# scoreboard.net
KiCad netlist of a schematic drawn in EAGLE
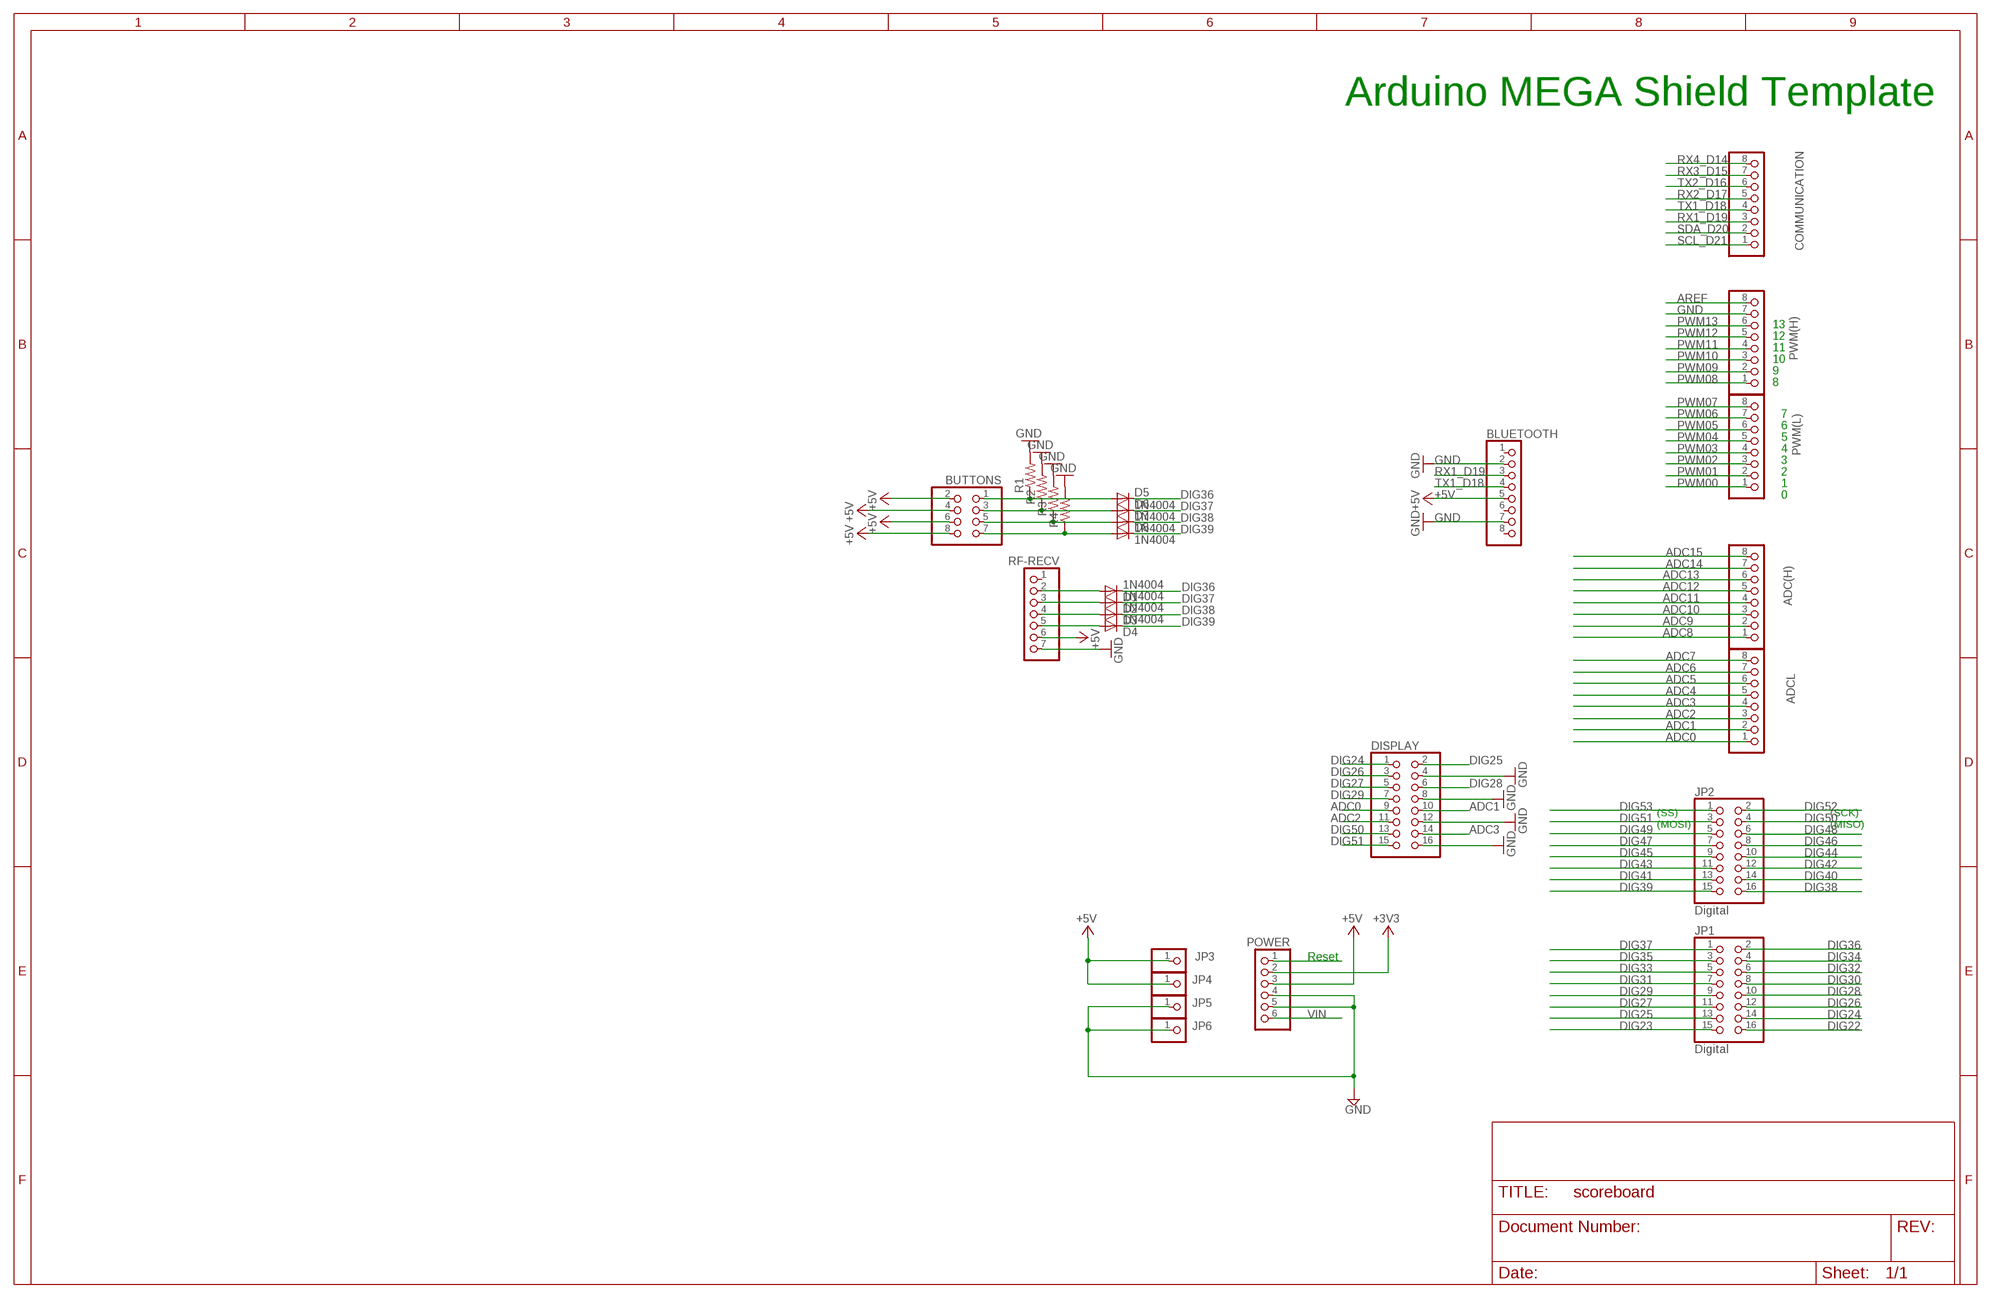
[diagram p0: schematic, sheet 1]

(export (version "E")
  (design (tool "Eeschema 10.0.6"))
  (components
    (comp (ref "ADC(H)")
      (value "PINHD-1X8")
      (footprint "eagle-import:1X08")
      (libsource (lib "eagle-import") (part "PINHD-1X8"))
    )
    (comp (ref "ADCL")
      (value "PINHD-1X8")
      (footprint "eagle-import:1X08")
      (libsource (lib "eagle-import") (part "PINHD-1X8"))
    )
    (comp (ref "BLUETOOTH")
      (value "PINHD-1X8")
      (footprint "eagle-import:1X08")
      (libsource (lib "eagle-import") (part "PINHD-1X8"))
    )
    (comp (ref "BUTTONS")
      (value "PINHD-2X4")
      (footprint "eagle-import:2X04")
      (libsource (lib "eagle-import") (part "PINHD-2X4"))
    )
    (comp (ref "COMMUNICATION")
      (value "PINHD-1X8")
      (footprint "eagle-import:1X08")
      (libsource (lib "eagle-import") (part "PINHD-1X8"))
    )
    (comp (ref "D1")
      (value "1N4004")
      (footprint "eagle-import:DO41-10")
      (libsource (lib "eagle-import") (part "1N4004"))
    )
    (comp (ref "D2")
      (value "1N4004")
      (footprint "eagle-import:DO41-10")
      (libsource (lib "eagle-import") (part "1N4004"))
    )
    (comp (ref "D3")
      (value "1N4004")
      (footprint "eagle-import:DO41-10")
      (libsource (lib "eagle-import") (part "1N4004"))
    )
    (comp (ref "D4")
      (value "1N4004")
      (footprint "eagle-import:DO41-10")
      (libsource (lib "eagle-import") (part "1N4004"))
    )
    (comp (ref "D5")
      (value "1N4004")
      (footprint "eagle-import:DO41-10")
      (libsource (lib "eagle-import") (part "1N4004"))
    )
    (comp (ref "D6")
      (value "1N4004")
      (footprint "eagle-import:DO41-10")
      (libsource (lib "eagle-import") (part "1N4004"))
    )
    (comp (ref "D7")
      (value "1N4004")
      (footprint "eagle-import:DO41-10")
      (libsource (lib "eagle-import") (part "1N4004"))
    )
    (comp (ref "D8")
      (value "1N4004")
      (footprint "eagle-import:DO41-10")
      (libsource (lib "eagle-import") (part "1N4004"))
    )
    (comp (ref "DISPLAY")
      (value "PINHD-2X8")
      (footprint "eagle-import:2X08")
      (libsource (lib "eagle-import") (part "PINHD-2X8"))
    )
    (comp (ref "JP1")
      (value "Digital")
      (footprint "eagle-import:2X08")
      (libsource (lib "eagle-import") (part "PINHD-2X8"))
    )
    (comp (ref "JP2")
      (value "Digital")
      (footprint "eagle-import:2X08")
      (libsource (lib "eagle-import") (part "PINHD-2X8"))
    )
    (comp (ref "JP3")
      (value "PINHD-1X1")
      (footprint "eagle-import:1X01")
      (libsource (lib "eagle-import") (part "PINHD-1X1"))
    )
    (comp (ref "JP4")
      (value "PINHD-1X1")
      (footprint "eagle-import:1X01")
      (libsource (lib "eagle-import") (part "PINHD-1X1"))
    )
    (comp (ref "JP5")
      (value "PINHD-1X1")
      (footprint "eagle-import:1X01")
      (libsource (lib "eagle-import") (part "PINHD-1X1"))
    )
    (comp (ref "JP6")
      (value "PINHD-1X1")
      (footprint "eagle-import:1X01")
      (libsource (lib "eagle-import") (part "PINHD-1X1"))
    )
    (comp (ref "POWER")
      (value "PINHD-1X6")
      (footprint "eagle-import:1X06")
      (libsource (lib "eagle-import") (part "PINHD-1X6"))
    )
    (comp (ref "PWM(H)")
      (value "PINHD-1X8")
      (footprint "eagle-import:1X08")
      (libsource (lib "eagle-import") (part "PINHD-1X8"))
    )
    (comp (ref "PWM(L)")
      (value "PINHD-1X8")
      (footprint "eagle-import:1X08")
      (libsource (lib "eagle-import") (part "PINHD-1X8"))
    )
    (comp (ref "R1")
      (value "FLIPFLOP-RES")
      (footprint "eagle-import:0805-THM")
      (libsource (lib "eagle-import") (part "FLIPFLOP-RES"))
    )
    (comp (ref "R2")
      (value "FLIPFLOP-RES")
      (footprint "eagle-import:0805-THM")
      (libsource (lib "eagle-import") (part "FLIPFLOP-RES"))
    )
    (comp (ref "R3")
      (value "FLIPFLOP-RES")
      (footprint "eagle-import:0805-THM")
      (libsource (lib "eagle-import") (part "FLIPFLOP-RES"))
    )
    (comp (ref "R4")
      (value "FLIPFLOP-RES")
      (footprint "eagle-import:0805-THM")
      (libsource (lib "eagle-import") (part "FLIPFLOP-RES"))
    )
    (comp (ref "RF-RECV")
      (value "PINHD-1X7")
      (footprint "eagle-import:1X07")
      (libsource (lib "eagle-import") (part "PINHD-1X7"))
    )
  )
  (nets
    (net (code "1") (name "+3V3") (class "Default")
      (node (ref "POWER") (pin "2") (pinfunction "2_2") (pintype "passive"))
    )
    (net (code "2") (name "+5V") (class "Default")
      (node (ref "BLUETOOTH") (pin "5") (pinfunction "5_5") (pintype "passive"))
      (node (ref "BUTTONS") (pin "2") (pinfunction "2_2") (pintype "passive"))
      (node (ref "BUTTONS") (pin "4") (pinfunction "4_4") (pintype "passive"))
      (node (ref "BUTTONS") (pin "6") (pinfunction "6_6") (pintype "passive"))
      (node (ref "BUTTONS") (pin "8") (pinfunction "8_8") (pintype "passive"))
      (node (ref "JP3") (pin "1") (pinfunction "1_1") (pintype "passive"))
      (node (ref "JP4") (pin "1") (pinfunction "1_1") (pintype "passive"))
      (node (ref "POWER") (pin "3") (pinfunction "3_3") (pintype "passive"))
      (node (ref "RF-RECV") (pin "6") (pinfunction "6_6") (pintype "passive"))
    )
    (net (code "3") (name "/ADC0") (class "Default")
      (node (ref "ADCL") (pin "1") (pinfunction "1_1") (pintype "passive"))
      (node (ref "DISPLAY") (pin "9") (pinfunction "9_9") (pintype "passive"))
    )
    (net (code "4") (name "/ADC1") (class "Default")
      (node (ref "ADCL") (pin "2") (pinfunction "2_2") (pintype "passive"))
      (node (ref "DISPLAY") (pin "10") (pinfunction "10_10") (pintype "passive"))
    )
    (net (code "5") (name "/ADC2") (class "Default")
      (node (ref "ADCL") (pin "3") (pinfunction "3_3") (pintype "passive"))
      (node (ref "DISPLAY") (pin "11") (pinfunction "11_11") (pintype "passive"))
    )
    (net (code "6") (name "/ADC3") (class "Default")
      (node (ref "ADCL") (pin "4") (pinfunction "4_4") (pintype "passive"))
      (node (ref "DISPLAY") (pin "14") (pinfunction "14_14") (pintype "passive"))
    )
    (net (code "7") (name "/ADC4") (class "Default")
      (node (ref "ADCL") (pin "5") (pinfunction "5_5") (pintype "passive"))
    )
    (net (code "8") (name "/ADC5") (class "Default")
      (node (ref "ADCL") (pin "6") (pinfunction "6_6") (pintype "passive"))
    )
    (net (code "9") (name "/ADC6") (class "Default")
      (node (ref "ADCL") (pin "7") (pinfunction "7_7") (pintype "passive"))
    )
    (net (code "10") (name "/ADC7") (class "Default")
      (node (ref "ADCL") (pin "8") (pinfunction "8_8") (pintype "passive"))
    )
    (net (code "11") (name "/ADC8") (class "Default")
      (node (ref "ADC(H)") (pin "1") (pinfunction "1_1") (pintype "passive"))
    )
    (net (code "12") (name "/ADC9") (class "Default")
      (node (ref "ADC(H)") (pin "2") (pinfunction "2_2") (pintype "passive"))
    )
    (net (code "13") (name "/ADC10") (class "Default")
      (node (ref "ADC(H)") (pin "3") (pinfunction "3_3") (pintype "passive"))
    )
    (net (code "14") (name "/ADC11") (class "Default")
      (node (ref "ADC(H)") (pin "4") (pinfunction "4_4") (pintype "passive"))
    )
    (net (code "15") (name "/ADC12") (class "Default")
      (node (ref "ADC(H)") (pin "5") (pinfunction "5_5") (pintype "passive"))
    )
    (net (code "16") (name "/ADC13") (class "Default")
      (node (ref "ADC(H)") (pin "6") (pinfunction "6_6") (pintype "passive"))
    )
    (net (code "17") (name "/ADC14") (class "Default")
      (node (ref "ADC(H)") (pin "7") (pinfunction "7_7") (pintype "passive"))
    )
    (net (code "18") (name "/ADC15") (class "Default")
      (node (ref "ADC(H)") (pin "8") (pinfunction "8_8") (pintype "passive"))
    )
    (net (code "19") (name "/AREF") (class "Default")
      (node (ref "PWM(H)") (pin "8") (pinfunction "8_8") (pintype "passive"))
    )
    (net (code "20") (name "/DIG22") (class "Default")
      (node (ref "JP1") (pin "16") (pinfunction "16_16") (pintype "passive"))
    )
    (net (code "21") (name "/DIG23") (class "Default")
      (node (ref "JP1") (pin "15") (pinfunction "15_15") (pintype "passive"))
    )
    (net (code "22") (name "/DIG24") (class "Default")
      (node (ref "DISPLAY") (pin "1") (pinfunction "1_1") (pintype "passive"))
      (node (ref "JP1") (pin "14") (pinfunction "14_14") (pintype "passive"))
    )
    (net (code "23") (name "/DIG25") (class "Default")
      (node (ref "DISPLAY") (pin "2") (pinfunction "2_2") (pintype "passive"))
      (node (ref "JP1") (pin "13") (pinfunction "13_13") (pintype "passive"))
    )
    (net (code "24") (name "/DIG26") (class "Default")
      (node (ref "DISPLAY") (pin "3") (pinfunction "3_3") (pintype "passive"))
      (node (ref "JP1") (pin "12") (pinfunction "12_12") (pintype "passive"))
    )
    (net (code "25") (name "/DIG27") (class "Default")
      (node (ref "DISPLAY") (pin "5") (pinfunction "5_5") (pintype "passive"))
      (node (ref "JP1") (pin "11") (pinfunction "11_11") (pintype "passive"))
    )
    (net (code "26") (name "/DIG28") (class "Default")
      (node (ref "DISPLAY") (pin "6") (pinfunction "6_6") (pintype "passive"))
      (node (ref "JP1") (pin "10") (pinfunction "10_10") (pintype "passive"))
    )
    (net (code "27") (name "/DIG29") (class "Default")
      (node (ref "DISPLAY") (pin "7") (pinfunction "7_7") (pintype "passive"))
      (node (ref "JP1") (pin "9") (pinfunction "9_9") (pintype "passive"))
    )
    (net (code "28") (name "/DIG30") (class "Default")
      (node (ref "JP1") (pin "8") (pinfunction "8_8") (pintype "passive"))
    )
    (net (code "29") (name "/DIG31") (class "Default")
      (node (ref "JP1") (pin "7") (pinfunction "7_7") (pintype "passive"))
    )
    (net (code "30") (name "/DIG32") (class "Default")
      (node (ref "JP1") (pin "6") (pinfunction "6_6") (pintype "passive"))
    )
    (net (code "31") (name "/DIG33") (class "Default")
      (node (ref "JP1") (pin "5") (pinfunction "5_5") (pintype "passive"))
    )
    (net (code "32") (name "/DIG34") (class "Default")
      (node (ref "JP1") (pin "4") (pinfunction "4_4") (pintype "passive"))
    )
    (net (code "33") (name "/DIG35") (class "Default")
      (node (ref "JP1") (pin "3") (pinfunction "3_3") (pintype "passive"))
    )
    (net (code "34") (name "/DIG36") (class "Default")
      (node (ref "D1") (pin "C") (pinfunction "C_C") (pintype "passive"))
      (node (ref "D5") (pin "C") (pinfunction "C_C") (pintype "passive"))
      (node (ref "JP1") (pin "2") (pinfunction "2_2") (pintype "passive"))
    )
    (net (code "35") (name "/DIG37") (class "Default")
      (node (ref "D2") (pin "C") (pinfunction "C_C") (pintype "passive"))
      (node (ref "D6") (pin "C") (pinfunction "C_C") (pintype "passive"))
      (node (ref "JP1") (pin "1") (pinfunction "1_1") (pintype "passive"))
    )
    (net (code "36") (name "/DIG38") (class "Default")
      (node (ref "D3") (pin "C") (pinfunction "C_C") (pintype "passive"))
      (node (ref "D7") (pin "C") (pinfunction "C_C") (pintype "passive"))
      (node (ref "JP2") (pin "16") (pinfunction "16_16") (pintype "passive"))
    )
    (net (code "37") (name "/DIG39") (class "Default")
      (node (ref "D4") (pin "C") (pinfunction "C_C") (pintype "passive"))
      (node (ref "D8") (pin "C") (pinfunction "C_C") (pintype "passive"))
      (node (ref "JP2") (pin "15") (pinfunction "15_15") (pintype "passive"))
    )
    (net (code "38") (name "/DIG40") (class "Default")
      (node (ref "JP2") (pin "14") (pinfunction "14_14") (pintype "passive"))
    )
    (net (code "39") (name "/DIG41") (class "Default")
      (node (ref "JP2") (pin "13") (pinfunction "13_13") (pintype "passive"))
    )
    (net (code "40") (name "/DIG42") (class "Default")
      (node (ref "JP2") (pin "12") (pinfunction "12_12") (pintype "passive"))
    )
    (net (code "41") (name "/DIG43") (class "Default")
      (node (ref "JP2") (pin "11") (pinfunction "11_11") (pintype "passive"))
    )
    (net (code "42") (name "/DIG44") (class "Default")
      (node (ref "JP2") (pin "10") (pinfunction "10_10") (pintype "passive"))
    )
    (net (code "43") (name "/DIG45") (class "Default")
      (node (ref "JP2") (pin "9") (pinfunction "9_9") (pintype "passive"))
    )
    (net (code "44") (name "/DIG46") (class "Default")
      (node (ref "JP2") (pin "8") (pinfunction "8_8") (pintype "passive"))
    )
    (net (code "45") (name "/DIG47") (class "Default")
      (node (ref "JP2") (pin "7") (pinfunction "7_7") (pintype "passive"))
    )
    (net (code "46") (name "/DIG48") (class "Default")
      (node (ref "JP2") (pin "6") (pinfunction "6_6") (pintype "passive"))
    )
    (net (code "47") (name "/DIG49") (class "Default")
      (node (ref "JP2") (pin "5") (pinfunction "5_5") (pintype "passive"))
    )
    (net (code "48") (name "/DIG50") (class "Default")
      (node (ref "DISPLAY") (pin "13") (pinfunction "13_13") (pintype "passive"))
      (node (ref "JP2") (pin "4") (pinfunction "4_4") (pintype "passive"))
    )
    (net (code "49") (name "/DIG51") (class "Default")
      (node (ref "DISPLAY") (pin "15") (pinfunction "15_15") (pintype "passive"))
      (node (ref "JP2") (pin "3") (pinfunction "3_3") (pintype "passive"))
    )
    (net (code "50") (name "/DIG52") (class "Default")
      (node (ref "JP2") (pin "2") (pinfunction "2_2") (pintype "passive"))
    )
    (net (code "51") (name "/DIG53") (class "Default")
      (node (ref "JP2") (pin "1") (pinfunction "1_1") (pintype "passive"))
    )
    (net (code "52") (name "/PWM00") (class "Default")
      (node (ref "PWM(L)") (pin "1") (pinfunction "1_1") (pintype "passive"))
    )
    (net (code "53") (name "/PWM01") (class "Default")
      (node (ref "PWM(L)") (pin "2") (pinfunction "2_2") (pintype "passive"))
    )
    (net (code "54") (name "/PWM02") (class "Default")
      (node (ref "PWM(L)") (pin "3") (pinfunction "3_3") (pintype "passive"))
    )
    (net (code "55") (name "/PWM03") (class "Default")
      (node (ref "PWM(L)") (pin "4") (pinfunction "4_4") (pintype "passive"))
    )
    (net (code "56") (name "/PWM04") (class "Default")
      (node (ref "PWM(L)") (pin "5") (pinfunction "5_5") (pintype "passive"))
    )
    (net (code "57") (name "/PWM05") (class "Default")
      (node (ref "PWM(L)") (pin "6") (pinfunction "6_6") (pintype "passive"))
    )
    (net (code "58") (name "/PWM06") (class "Default")
      (node (ref "PWM(L)") (pin "7") (pinfunction "7_7") (pintype "passive"))
    )
    (net (code "59") (name "/PWM07") (class "Default")
      (node (ref "PWM(L)") (pin "8") (pinfunction "8_8") (pintype "passive"))
    )
    (net (code "60") (name "/PWM08") (class "Default")
      (node (ref "PWM(H)") (pin "1") (pinfunction "1_1") (pintype "passive"))
    )
    (net (code "61") (name "/PWM09") (class "Default")
      (node (ref "PWM(H)") (pin "2") (pinfunction "2_2") (pintype "passive"))
    )
    (net (code "62") (name "/PWM10") (class "Default")
      (node (ref "PWM(H)") (pin "3") (pinfunction "3_3") (pintype "passive"))
    )
    (net (code "63") (name "/PWM11") (class "Default")
      (node (ref "PWM(H)") (pin "4") (pinfunction "4_4") (pintype "passive"))
    )
    (net (code "64") (name "/PWM12") (class "Default")
      (node (ref "PWM(H)") (pin "5") (pinfunction "5_5") (pintype "passive"))
    )
    (net (code "65") (name "/PWM13") (class "Default")
      (node (ref "PWM(H)") (pin "6") (pinfunction "6_6") (pintype "passive"))
    )
    (net (code "66") (name "/RX1_D19") (class "Default")
      (node (ref "BLUETOOTH") (pin "3") (pinfunction "3_3") (pintype "passive"))
      (node (ref "COMMUNICATION") (pin "3") (pinfunction "3_3") (pintype "passive"))
    )
    (net (code "67") (name "/RX2_D17") (class "Default")
      (node (ref "COMMUNICATION") (pin "5") (pinfunction "5_5") (pintype "passive"))
    )
    (net (code "68") (name "/RX3_D15") (class "Default")
      (node (ref "COMMUNICATION") (pin "7") (pinfunction "7_7") (pintype "passive"))
    )
    (net (code "69") (name "/RX4_D14") (class "Default")
      (node (ref "COMMUNICATION") (pin "8") (pinfunction "8_8") (pintype "passive"))
    )
    (net (code "70") (name "/SCL_D21") (class "Default")
      (node (ref "COMMUNICATION") (pin "1") (pinfunction "1_1") (pintype "passive"))
    )
    (net (code "71") (name "/SDA_D20") (class "Default")
      (node (ref "COMMUNICATION") (pin "2") (pinfunction "2_2") (pintype "passive"))
    )
    (net (code "72") (name "/TX1_D18") (class "Default")
      (node (ref "BLUETOOTH") (pin "4") (pinfunction "4_4") (pintype "passive"))
      (node (ref "COMMUNICATION") (pin "4") (pinfunction "4_4") (pintype "passive"))
    )
    (net (code "73") (name "/TX2_D16") (class "Default")
      (node (ref "COMMUNICATION") (pin "6") (pinfunction "6_6") (pintype "passive"))
    )
    (net (code "74") (name "/VIN") (class "Default")
      (node (ref "POWER") (pin "6") (pinfunction "6_6") (pintype "passive"))
    )
    (net (code "75") (name "GND") (class "Default")
      (node (ref "BLUETOOTH") (pin "2") (pinfunction "2_2") (pintype "passive"))
      (node (ref "BLUETOOTH") (pin "7") (pinfunction "7_7") (pintype "passive"))
      (node (ref "DISPLAY") (pin "12") (pinfunction "12_12") (pintype "passive"))
      (node (ref "DISPLAY") (pin "16") (pinfunction "16_16") (pintype "passive"))
      (node (ref "DISPLAY") (pin "4") (pinfunction "4_4") (pintype "passive"))
      (node (ref "DISPLAY") (pin "8") (pinfunction "8_8") (pintype "passive"))
      (node (ref "JP5") (pin "1") (pinfunction "1_1") (pintype "passive"))
      (node (ref "JP6") (pin "1") (pinfunction "1_1") (pintype "passive"))
      (node (ref "POWER") (pin "4") (pinfunction "4_4") (pintype "passive"))
      (node (ref "POWER") (pin "5") (pinfunction "5_5") (pintype "passive"))
      (node (ref "PWM(H)") (pin "7") (pinfunction "7_7") (pintype "passive"))
      (node (ref "R1") (pin "2") (pinfunction "2_2") (pintype "passive"))
      (node (ref "R2") (pin "2") (pinfunction "2_2") (pintype "passive"))
      (node (ref "R3") (pin "2") (pinfunction "2_2") (pintype "passive"))
      (node (ref "R4") (pin "2") (pinfunction "2_2") (pintype "passive"))
      (node (ref "RF-RECV") (pin "7") (pinfunction "7_7") (pintype "passive"))
    )
    (net (code "76") (name "Net-(BUTTONS-Pad1)") (class "Default")
      (node (ref "BUTTONS") (pin "1") (pinfunction "1_1") (pintype "passive"))
      (node (ref "D5") (pin "A") (pinfunction "A_A") (pintype "passive"))
      (node (ref "R1") (pin "1") (pinfunction "1_1") (pintype "passive"))
    )
    (net (code "77") (name "Net-(BUTTONS-Pad3)") (class "Default")
      (node (ref "BUTTONS") (pin "3") (pinfunction "3_3") (pintype "passive"))
      (node (ref "D6") (pin "A") (pinfunction "A_A") (pintype "passive"))
      (node (ref "R2") (pin "1") (pinfunction "1_1") (pintype "passive"))
    )
    (net (code "78") (name "Net-(BUTTONS-Pad5)") (class "Default")
      (node (ref "BUTTONS") (pin "5") (pinfunction "5_5") (pintype "passive"))
      (node (ref "D7") (pin "A") (pinfunction "A_A") (pintype "passive"))
      (node (ref "R3") (pin "1") (pinfunction "1_1") (pintype "passive"))
    )
    (net (code "79") (name "Net-(BUTTONS-Pad7)") (class "Default")
      (node (ref "BUTTONS") (pin "7") (pinfunction "7_7") (pintype "passive"))
      (node (ref "D8") (pin "A") (pinfunction "A_A") (pintype "passive"))
      (node (ref "R4") (pin "1") (pinfunction "1_1") (pintype "passive"))
    )
    (net (code "80") (name "Net-(D1-PadA)") (class "Default")
      (node (ref "D1") (pin "A") (pinfunction "A_A") (pintype "passive"))
      (node (ref "RF-RECV") (pin "2") (pinfunction "2_2") (pintype "passive"))
    )
    (net (code "81") (name "Net-(D2-PadA)") (class "Default")
      (node (ref "D2") (pin "A") (pinfunction "A_A") (pintype "passive"))
      (node (ref "RF-RECV") (pin "3") (pinfunction "3_3") (pintype "passive"))
    )
    (net (code "82") (name "Net-(D3-PadA)") (class "Default")
      (node (ref "D3") (pin "A") (pinfunction "A_A") (pintype "passive"))
      (node (ref "RF-RECV") (pin "4") (pinfunction "4_4") (pintype "passive"))
    )
    (net (code "83") (name "Net-(D4-PadA)") (class "Default")
      (node (ref "D4") (pin "A") (pinfunction "A_A") (pintype "passive"))
      (node (ref "RF-RECV") (pin "5") (pinfunction "5_5") (pintype "passive"))
    )
    (net (code "84") (name "unconnected-(BLUETOOTH-Pad1)") (class "Default")
      (node (ref "BLUETOOTH") (pin "1") (pinfunction "1_1") (pintype "passive"))
    )
    (net (code "85") (name "unconnected-(BLUETOOTH-Pad6)") (class "Default")
      (node (ref "BLUETOOTH") (pin "6") (pinfunction "6_6") (pintype "passive"))
    )
    (net (code "86") (name "unconnected-(BLUETOOTH-Pad8)") (class "Default")
      (node (ref "BLUETOOTH") (pin "8") (pinfunction "8_8") (pintype "passive"))
    )
    (net (code "87") (name "unconnected-(POWER-Pad1)") (class "Default")
      (node (ref "POWER") (pin "1") (pinfunction "1_1") (pintype "passive"))
    )
    (net (code "88") (name "unconnected-(RF-RECV-Pad1)") (class "Default")
      (node (ref "RF-RECV") (pin "1") (pinfunction "1_1") (pintype "passive"))
    )
  )
)
